# LISC_SensorIO.net
KiCad netlist of a schematic drawn in Altium Designer
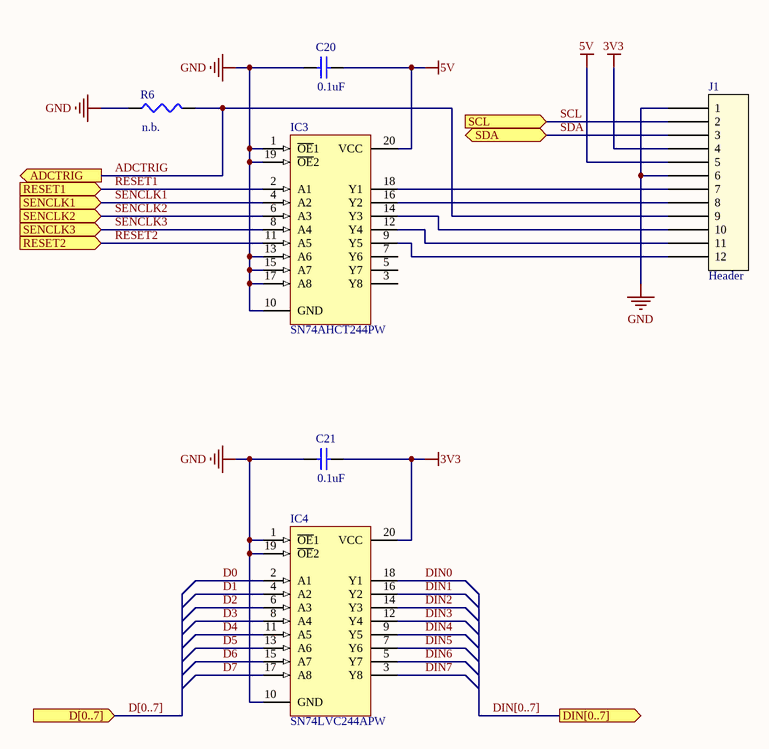
[diagram p0: LISC_SensorIO.SchDoc]

(export (version "E")
  (design (tool "Eeschema 10.0.6"))
  (components
    (comp (ref "C20")
      (value "0.1uF")
      (footprint "1608[0603]")
      (description "Capacitor (Semiconductor SIM Model)")
      (fields (field (name "PUBLISHER") "Altium Limited"))
      (libsource (lib "Miscellaneous Devices") (part "Cap Semi"))
    )
    (comp (ref "C21")
      (value "0.1uF")
      (footprint "1608[0603]")
      (description "Capacitor (Semiconductor SIM Model)")
      (fields (field (name "PUBLISHER") "Altium Limited"))
      (libsource (lib "Miscellaneous Devices") (part "Cap Semi"))
    )
    (comp (ref "IC3")
      (value "SN74AHCT244PW")
      (footprint "PW020_M")
      (description "Octal Buffer/Driver with 3-State Outputs")
      (fields (field (name "PUBLISHER") "Altium Limited"))
      (libsource (lib "TI Logic Buffer Line Driver") (part "SN74AHCT244PWLE"))
    )
    (comp (ref "IC4")
      (value "SN74LVC244APW")
      (footprint "PW020_M")
      (description "Octal Buffer/Driver with 3-State Outputs")
      (fields (field (name "PUBLISHER") "Altium Limited"))
      (libsource (lib "TI Logic Buffer Line Driver") (part "SN74LVC244APW"))
    )
    (comp (ref "J1")
      (value "Header")
      (footprint "Molex_Picoflex_12")
      (description "Molex Picoflex 12pol.")
      (libsource (lib "Connectors_MolexPicoflex") (part "Header"))
    )
    (comp (ref "R6")
      (value "n.b.")
      (footprint "J1-0603")
      (description "Resistor")
      (fields (field (name "PUBLISHER") "Altium Limited"))
      (libsource (lib "Miscellaneous Devices") (part "Res3"))
    )
  )
  (nets
    (net (code "1") (name "/ADCTRIG") (class "Default")
      (node (ref "J1") (pin "9") (pinfunction "9_9") (pintype "passive"))
      (node (ref "R6") (pin "2") (pinfunction "2_2") (pintype "passive"))
    )
    (net (code "2") (name "/D0") (class "Default")
      (node (ref "IC4") (pin "2") (pinfunction "A1_2") (pintype "input"))
    )
    (net (code "3") (name "/D1") (class "Default")
      (node (ref "IC4") (pin "4") (pinfunction "A2_4") (pintype "input"))
    )
    (net (code "4") (name "/D2") (class "Default")
      (node (ref "IC4") (pin "6") (pinfunction "A3_6") (pintype "input"))
    )
    (net (code "5") (name "/D3") (class "Default")
      (node (ref "IC4") (pin "8") (pinfunction "A4_8") (pintype "input"))
    )
    (net (code "6") (name "/D4") (class "Default")
      (node (ref "IC4") (pin "11") (pinfunction "A5_11") (pintype "input"))
    )
    (net (code "7") (name "/D5") (class "Default")
      (node (ref "IC4") (pin "13") (pinfunction "A6_13") (pintype "input"))
    )
    (net (code "8") (name "/D6") (class "Default")
      (node (ref "IC4") (pin "15") (pinfunction "A7_15") (pintype "input"))
    )
    (net (code "9") (name "/D7") (class "Default")
      (node (ref "IC4") (pin "17") (pinfunction "A8_17") (pintype "input"))
    )
    (net (code "10") (name "/DIN0") (class "Default")
      (node (ref "IC4") (pin "18") (pinfunction "Y1_18") (pintype "tri_state"))
    )
    (net (code "11") (name "/DIN1") (class "Default")
      (node (ref "IC4") (pin "16") (pinfunction "Y2_16") (pintype "tri_state"))
    )
    (net (code "12") (name "/DIN2") (class "Default")
      (node (ref "IC4") (pin "14") (pinfunction "Y3_14") (pintype "tri_state"))
    )
    (net (code "13") (name "/DIN3") (class "Default")
      (node (ref "IC4") (pin "12") (pinfunction "Y4_12") (pintype "tri_state"))
    )
    (net (code "14") (name "/DIN4") (class "Default")
      (node (ref "IC4") (pin "9") (pinfunction "Y5_9") (pintype "tri_state"))
    )
    (net (code "15") (name "/DIN5") (class "Default")
      (node (ref "IC4") (pin "7") (pinfunction "Y6_7") (pintype "tri_state"))
    )
    (net (code "16") (name "/DIN6") (class "Default")
      (node (ref "IC4") (pin "5") (pinfunction "Y7_5") (pintype "tri_state"))
    )
    (net (code "17") (name "/DIN7") (class "Default")
      (node (ref "IC4") (pin "3") (pinfunction "Y8_3") (pintype "tri_state"))
    )
    (net (code "20") (name "/RESET1") (class "Default")
      (node (ref "IC3") (pin "2") (pinfunction "A1_2") (pintype "input"))
    )
    (net (code "21") (name "/RESET2") (class "Default")
      (node (ref "IC3") (pin "11") (pinfunction "A5_11") (pintype "input"))
    )
    (net (code "22") (name "/SCL") (class "Default")
      (node (ref "J1") (pin "2") (pinfunction "2_2") (pintype "passive"))
    )
    (net (code "23") (name "/SDA") (class "Default")
      (node (ref "J1") (pin "3") (pinfunction "3_3") (pintype "passive"))
    )
    (net (code "24") (name "/SENCLK1") (class "Default")
      (node (ref "IC3") (pin "4") (pinfunction "A2_4") (pintype "input"))
    )
    (net (code "25") (name "/SENCLK2") (class "Default")
      (node (ref "IC3") (pin "6") (pinfunction "A3_6") (pintype "input"))
    )
    (net (code "26") (name "/SENCLK3") (class "Default")
      (node (ref "IC3") (pin "8") (pinfunction "A4_8") (pintype "input"))
    )
    (net (code "27") (name "3V3") (class "Default")
      (node (ref "C21") (pin "2") (pinfunction "2_2") (pintype "passive"))
      (node (ref "IC4") (pin "20") (pinfunction "VCC_20") (pintype "power_in"))
      (node (ref "J1") (pin "4") (pinfunction "4_4") (pintype "passive"))
    )
    (net (code "28") (name "5V") (class "Default")
      (node (ref "C20") (pin "2") (pinfunction "2_2") (pintype "passive"))
      (node (ref "IC3") (pin "20") (pinfunction "VCC_20") (pintype "power_in"))
      (node (ref "J1") (pin "5") (pinfunction "5_5") (pintype "passive"))
    )
    (net (code "29") (name "GND") (class "Default")
      (node (ref "C20") (pin "1") (pinfunction "1_1") (pintype "passive"))
      (node (ref "C21") (pin "1") (pinfunction "1_1") (pintype "passive"))
      (node (ref "IC3") (pin "1") (pinfunction "~{OE}1_1") (pintype "input"))
      (node (ref "IC3") (pin "10") (pinfunction "GND_10") (pintype "power_in"))
      (node (ref "IC3") (pin "13") (pinfunction "A6_13") (pintype "input"))
      (node (ref "IC3") (pin "15") (pinfunction "A7_15") (pintype "input"))
      (node (ref "IC3") (pin "17") (pinfunction "A8_17") (pintype "input"))
      (node (ref "IC3") (pin "19") (pinfunction "~{OE}2_19") (pintype "input"))
      (node (ref "IC4") (pin "1") (pinfunction "~{OE}1_1") (pintype "input"))
      (node (ref "IC4") (pin "10") (pinfunction "GND_10") (pintype "power_in"))
      (node (ref "IC4") (pin "19") (pinfunction "~{OE}2_19") (pintype "input"))
      (node (ref "J1") (pin "1") (pinfunction "1_1") (pintype "passive"))
      (node (ref "J1") (pin "6") (pinfunction "6_6") (pintype "passive"))
      (node (ref "R6") (pin "1") (pinfunction "1_1") (pintype "passive"))
    )
    (net (code "30") (name "Net-(IC3-Y1)") (class "Default")
      (node (ref "IC3") (pin "18") (pinfunction "Y1_18") (pintype "tri_state"))
      (node (ref "J1") (pin "7") (pinfunction "7_7") (pintype "passive"))
    )
    (net (code "31") (name "Net-(IC3-Y2)") (class "Default")
      (node (ref "IC3") (pin "16") (pinfunction "Y2_16") (pintype "tri_state"))
      (node (ref "J1") (pin "8") (pinfunction "8_8") (pintype "passive"))
    )
    (net (code "32") (name "Net-(IC3-Y3)") (class "Default")
      (node (ref "IC3") (pin "14") (pinfunction "Y3_14") (pintype "tri_state"))
      (node (ref "J1") (pin "10") (pinfunction "10_10") (pintype "passive"))
    )
    (net (code "33") (name "Net-(IC3-Y4)") (class "Default")
      (node (ref "IC3") (pin "12") (pinfunction "Y4_12") (pintype "tri_state"))
      (node (ref "J1") (pin "11") (pinfunction "11_11") (pintype "passive"))
    )
    (net (code "34") (name "Net-(IC3-Y5)") (class "Default")
      (node (ref "IC3") (pin "9") (pinfunction "Y5_9") (pintype "tri_state"))
      (node (ref "J1") (pin "12") (pinfunction "12_12") (pintype "passive"))
    )
    (net (code "35") (name "unconnected-(IC3-Y6-Pad7)") (class "Default")
      (node (ref "IC3") (pin "7") (pinfunction "Y6_7") (pintype "tri_state"))
    )
    (net (code "36") (name "unconnected-(IC3-Y7-Pad5)") (class "Default")
      (node (ref "IC3") (pin "5") (pinfunction "Y7_5") (pintype "tri_state"))
    )
    (net (code "37") (name "unconnected-(IC3-Y8-Pad3)") (class "Default")
      (node (ref "IC3") (pin "3") (pinfunction "Y8_3") (pintype "tri_state"))
    )
  )
)
